# sa_input.net
KiCad netlist of a schematic drawn in EAGLE
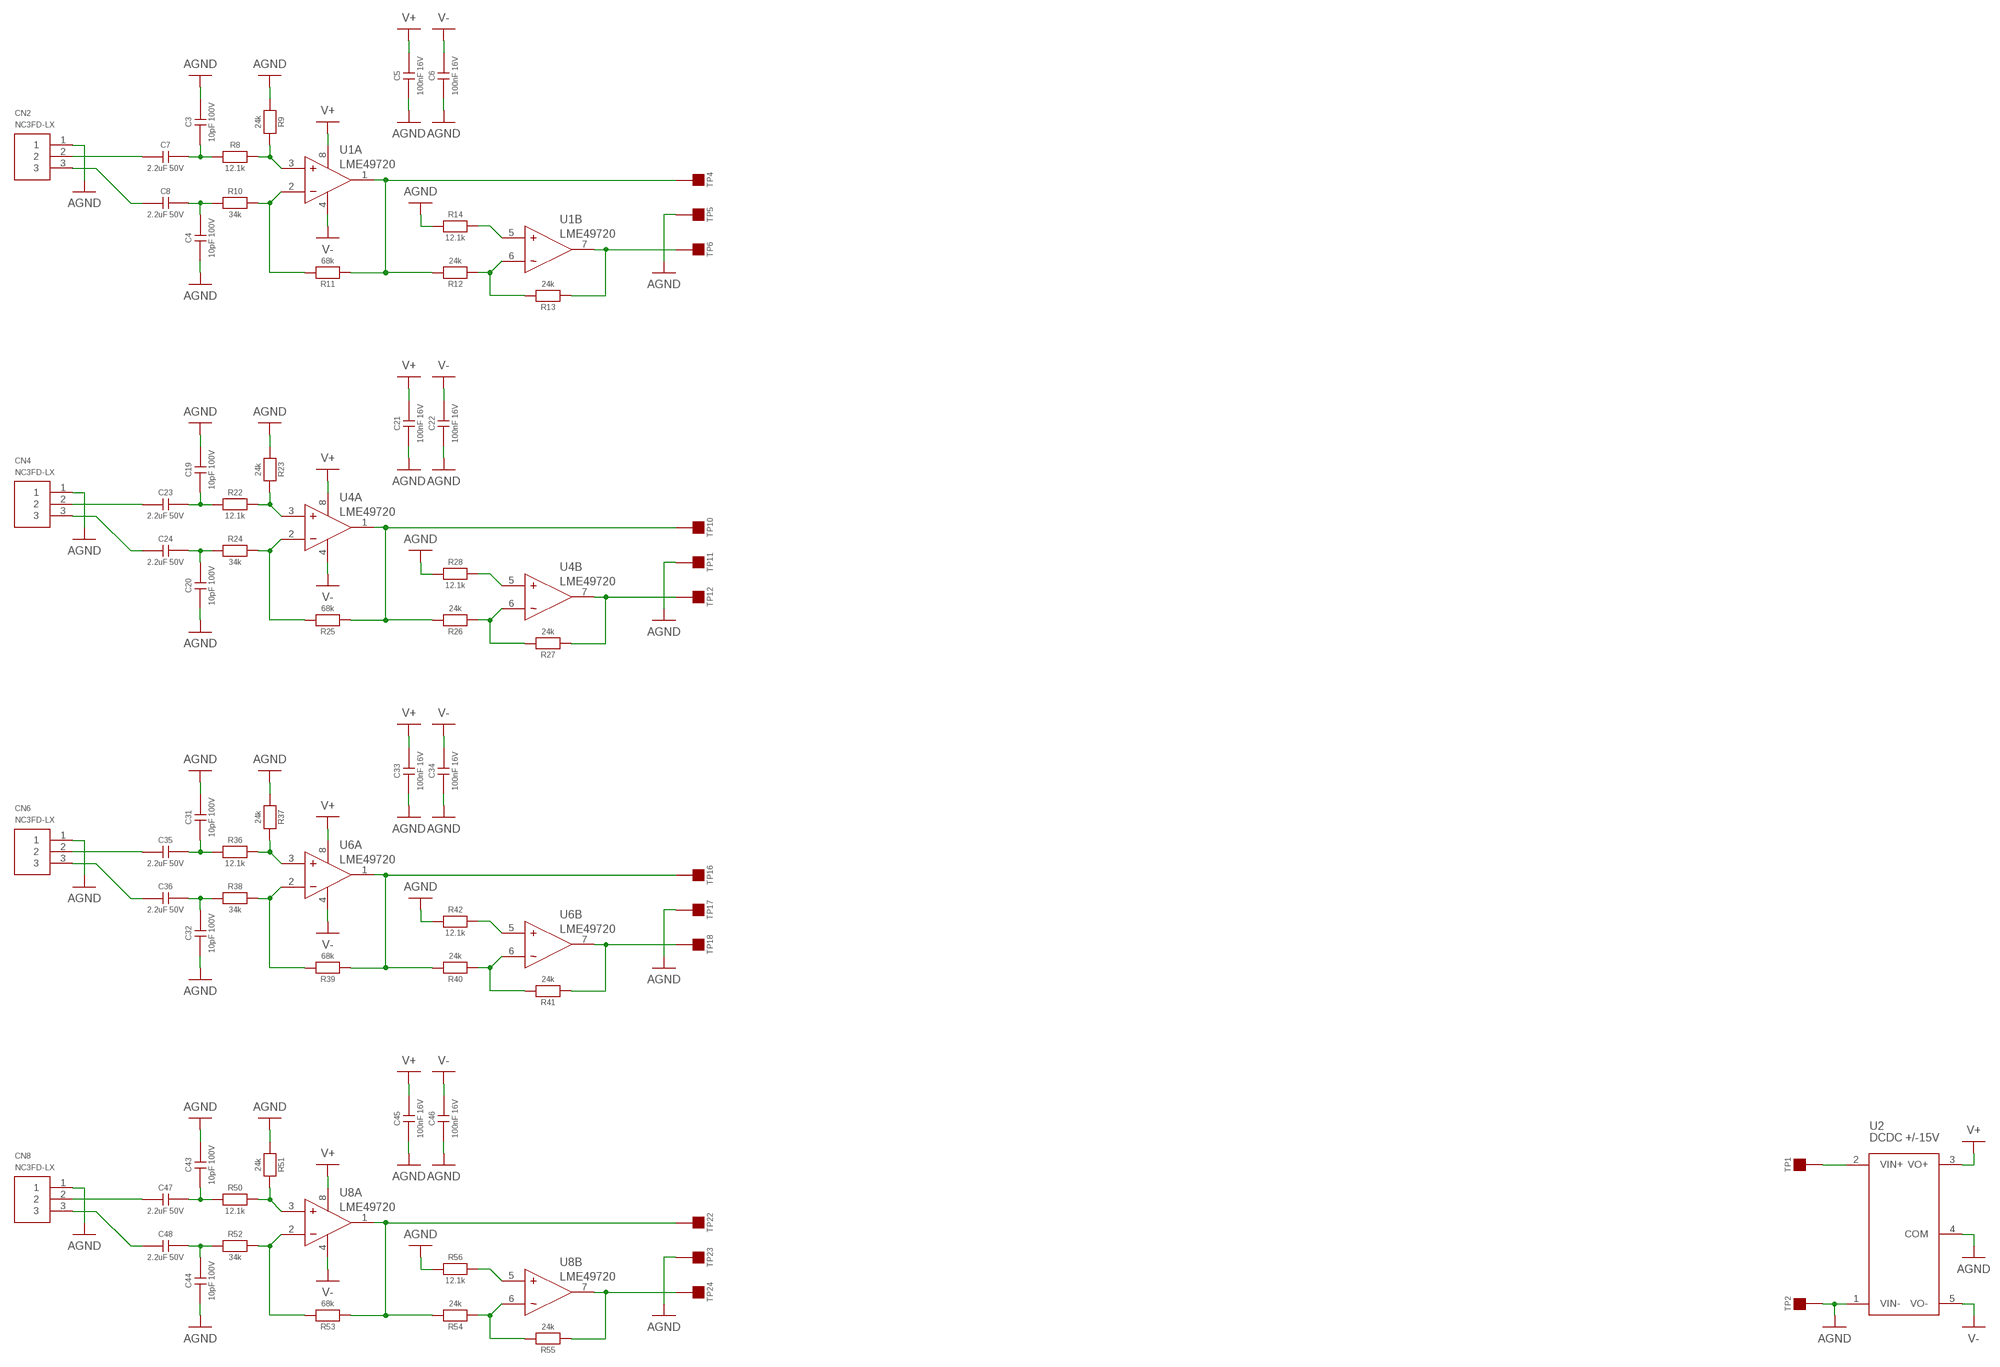
[diagram p0: schematic, sheet 1, part 1 of 2]
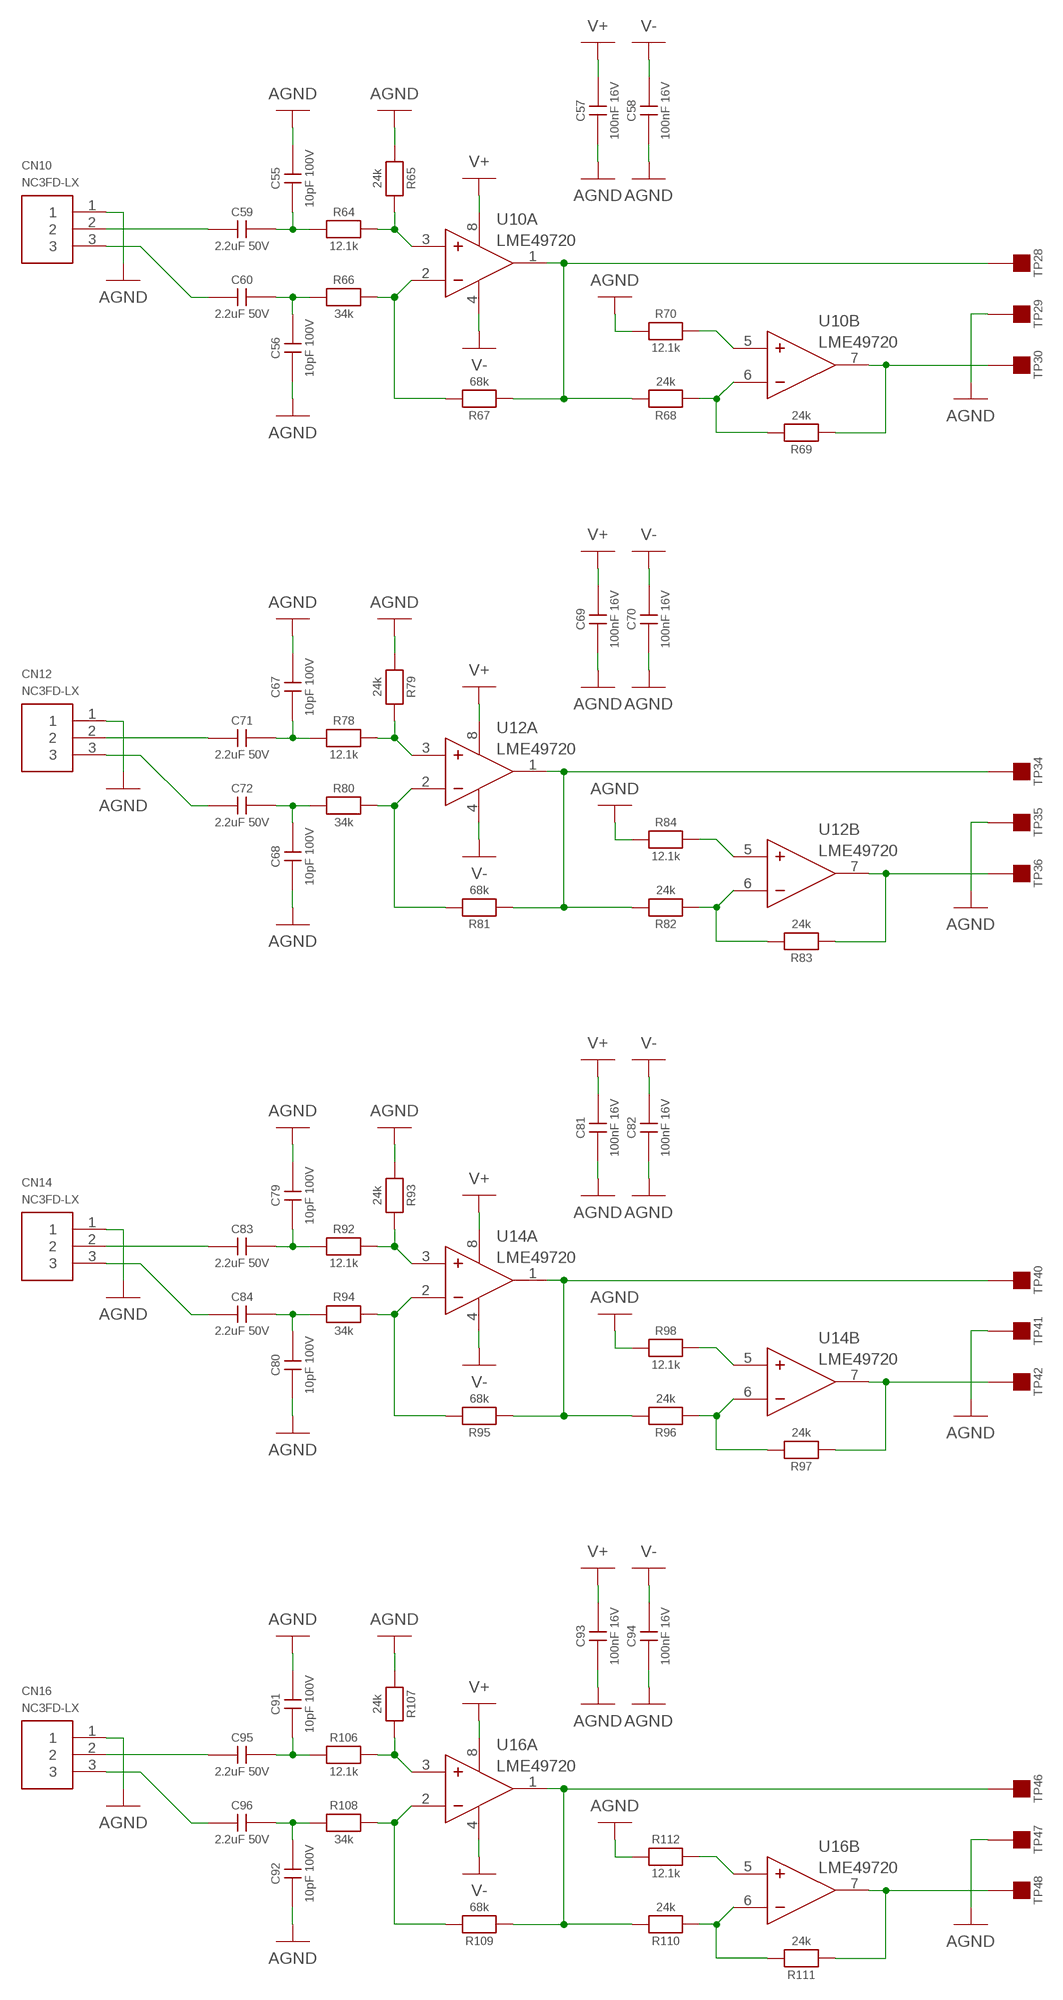
[diagram p1: schematic, sheet 1, part 2 of 2]

(export (version "E")
  (design (tool "Eeschema 10.0.6"))
  (components
    (comp (ref "C3")
      (value "10pF 100V")
      (footprint "eagle-import:0603")
      (libsource (lib "eagle-import") (part "06031A100FAT2A"))
    )
    (comp (ref "C4")
      (value "10pF 100V")
      (footprint "eagle-import:0603")
      (libsource (lib "eagle-import") (part "06031A100FAT2A"))
    )
    (comp (ref "C5")
      (value "100nF 16V")
      (footprint "eagle-import:0603")
      (libsource (lib "eagle-import") (part "CL10B104KO8WPNC"))
    )
    (comp (ref "C6")
      (value "100nF 16V")
      (footprint "eagle-import:0603")
      (libsource (lib "eagle-import") (part "CL10B104KO8WPNC"))
    )
    (comp (ref "C7")
      (value "2.2uF 50V")
      (footprint "eagle-import:5X7.2BOX")
      (libsource (lib "eagle-import") (part "MKS2B042201F00KSSD"))
    )
    (comp (ref "C8")
      (value "2.2uF 50V")
      (footprint "eagle-import:5X7.2BOX")
      (libsource (lib "eagle-import") (part "MKS2B042201F00KSSD"))
    )
    (comp (ref "C19")
      (value "10pF 100V")
      (footprint "eagle-import:0603")
      (libsource (lib "eagle-import") (part "06031A100FAT2A"))
    )
    (comp (ref "C20")
      (value "10pF 100V")
      (footprint "eagle-import:0603")
      (libsource (lib "eagle-import") (part "06031A100FAT2A"))
    )
    (comp (ref "C21")
      (value "100nF 16V")
      (footprint "eagle-import:0603")
      (libsource (lib "eagle-import") (part "CL10B104KO8WPNC"))
    )
    (comp (ref "C22")
      (value "100nF 16V")
      (footprint "eagle-import:0603")
      (libsource (lib "eagle-import") (part "CL10B104KO8WPNC"))
    )
    (comp (ref "C23")
      (value "2.2uF 50V")
      (footprint "eagle-import:5X7.2BOX")
      (libsource (lib "eagle-import") (part "MKS2B042201F00KSSD"))
    )
    (comp (ref "C24")
      (value "2.2uF 50V")
      (footprint "eagle-import:5X7.2BOX")
      (libsource (lib "eagle-import") (part "MKS2B042201F00KSSD"))
    )
    (comp (ref "C31")
      (value "10pF 100V")
      (footprint "eagle-import:0603")
      (libsource (lib "eagle-import") (part "06031A100FAT2A"))
    )
    (comp (ref "C32")
      (value "10pF 100V")
      (footprint "eagle-import:0603")
      (libsource (lib "eagle-import") (part "06031A100FAT2A"))
    )
    (comp (ref "C33")
      (value "100nF 16V")
      (footprint "eagle-import:0603")
      (libsource (lib "eagle-import") (part "CL10B104KO8WPNC"))
    )
    (comp (ref "C34")
      (value "100nF 16V")
      (footprint "eagle-import:0603")
      (libsource (lib "eagle-import") (part "CL10B104KO8WPNC"))
    )
    (comp (ref "C35")
      (value "2.2uF 50V")
      (footprint "eagle-import:5X7.2BOX")
      (libsource (lib "eagle-import") (part "MKS2B042201F00KSSD"))
    )
    (comp (ref "C36")
      (value "2.2uF 50V")
      (footprint "eagle-import:5X7.2BOX")
      (libsource (lib "eagle-import") (part "MKS2B042201F00KSSD"))
    )
    (comp (ref "C43")
      (value "10pF 100V")
      (footprint "eagle-import:0603")
      (libsource (lib "eagle-import") (part "06031A100FAT2A"))
    )
    (comp (ref "C44")
      (value "10pF 100V")
      (footprint "eagle-import:0603")
      (libsource (lib "eagle-import") (part "06031A100FAT2A"))
    )
    (comp (ref "C45")
      (value "100nF 16V")
      (footprint "eagle-import:0603")
      (libsource (lib "eagle-import") (part "CL10B104KO8WPNC"))
    )
    (comp (ref "C46")
      (value "100nF 16V")
      (footprint "eagle-import:0603")
      (libsource (lib "eagle-import") (part "CL10B104KO8WPNC"))
    )
    (comp (ref "C47")
      (value "2.2uF 50V")
      (footprint "eagle-import:5X7.2BOX")
      (libsource (lib "eagle-import") (part "MKS2B042201F00KSSD"))
    )
    (comp (ref "C48")
      (value "2.2uF 50V")
      (footprint "eagle-import:5X7.2BOX")
      (libsource (lib "eagle-import") (part "MKS2B042201F00KSSD"))
    )
    (comp (ref "C55")
      (value "10pF 100V")
      (footprint "eagle-import:0603")
      (libsource (lib "eagle-import") (part "06031A100FAT2A"))
    )
    (comp (ref "C56")
      (value "10pF 100V")
      (footprint "eagle-import:0603")
      (libsource (lib "eagle-import") (part "06031A100FAT2A"))
    )
    (comp (ref "C57")
      (value "100nF 16V")
      (footprint "eagle-import:0603")
      (libsource (lib "eagle-import") (part "CL10B104KO8WPNC"))
    )
    (comp (ref "C58")
      (value "100nF 16V")
      (footprint "eagle-import:0603")
      (libsource (lib "eagle-import") (part "CL10B104KO8WPNC"))
    )
    (comp (ref "C59")
      (value "2.2uF 50V")
      (footprint "eagle-import:5X7.2BOX")
      (libsource (lib "eagle-import") (part "MKS2B042201F00KSSD"))
    )
    (comp (ref "C60")
      (value "2.2uF 50V")
      (footprint "eagle-import:5X7.2BOX")
      (libsource (lib "eagle-import") (part "MKS2B042201F00KSSD"))
    )
    (comp (ref "C67")
      (value "10pF 100V")
      (footprint "eagle-import:0603")
      (libsource (lib "eagle-import") (part "06031A100FAT2A"))
    )
    (comp (ref "C68")
      (value "10pF 100V")
      (footprint "eagle-import:0603")
      (libsource (lib "eagle-import") (part "06031A100FAT2A"))
    )
    (comp (ref "C69")
      (value "100nF 16V")
      (footprint "eagle-import:0603")
      (libsource (lib "eagle-import") (part "CL10B104KO8WPNC"))
    )
    (comp (ref "C70")
      (value "100nF 16V")
      (footprint "eagle-import:0603")
      (libsource (lib "eagle-import") (part "CL10B104KO8WPNC"))
    )
    (comp (ref "C71")
      (value "2.2uF 50V")
      (footprint "eagle-import:5X7.2BOX")
      (libsource (lib "eagle-import") (part "MKS2B042201F00KSSD"))
    )
    (comp (ref "C72")
      (value "2.2uF 50V")
      (footprint "eagle-import:5X7.2BOX")
      (libsource (lib "eagle-import") (part "MKS2B042201F00KSSD"))
    )
    (comp (ref "C79")
      (value "10pF 100V")
      (footprint "eagle-import:0603")
      (libsource (lib "eagle-import") (part "06031A100FAT2A"))
    )
    (comp (ref "C80")
      (value "10pF 100V")
      (footprint "eagle-import:0603")
      (libsource (lib "eagle-import") (part "06031A100FAT2A"))
    )
    (comp (ref "C81")
      (value "100nF 16V")
      (footprint "eagle-import:0603")
      (libsource (lib "eagle-import") (part "CL10B104KO8WPNC"))
    )
    (comp (ref "C82")
      (value "100nF 16V")
      (footprint "eagle-import:0603")
      (libsource (lib "eagle-import") (part "CL10B104KO8WPNC"))
    )
    (comp (ref "C83")
      (value "2.2uF 50V")
      (footprint "eagle-import:5X7.2BOX")
      (libsource (lib "eagle-import") (part "MKS2B042201F00KSSD"))
    )
    (comp (ref "C84")
      (value "2.2uF 50V")
      (footprint "eagle-import:5X7.2BOX")
      (libsource (lib "eagle-import") (part "MKS2B042201F00KSSD"))
    )
    (comp (ref "C91")
      (value "10pF 100V")
      (footprint "eagle-import:0603")
      (libsource (lib "eagle-import") (part "06031A100FAT2A"))
    )
    (comp (ref "C92")
      (value "10pF 100V")
      (footprint "eagle-import:0603")
      (libsource (lib "eagle-import") (part "06031A100FAT2A"))
    )
    (comp (ref "C93")
      (value "100nF 16V")
      (footprint "eagle-import:0603")
      (libsource (lib "eagle-import") (part "CL10B104KO8WPNC"))
    )
    (comp (ref "C94")
      (value "100nF 16V")
      (footprint "eagle-import:0603")
      (libsource (lib "eagle-import") (part "CL10B104KO8WPNC"))
    )
    (comp (ref "C95")
      (value "2.2uF 50V")
      (footprint "eagle-import:5X7.2BOX")
      (libsource (lib "eagle-import") (part "MKS2B042201F00KSSD"))
    )
    (comp (ref "C96")
      (value "2.2uF 50V")
      (footprint "eagle-import:5X7.2BOX")
      (libsource (lib "eagle-import") (part "MKS2B042201F00KSSD"))
    )
    (comp (ref "CN2")
      (value "NC3FD-LX")
      (footprint "eagle-import:NC3FD-LX")
      (libsource (lib "eagle-import") (part "NC3FD-LX"))
    )
    (comp (ref "CN4")
      (value "NC3FD-LX")
      (footprint "eagle-import:NC3FD-LX")
      (libsource (lib "eagle-import") (part "NC3FD-LX"))
    )
    (comp (ref "CN6")
      (value "NC3FD-LX")
      (footprint "eagle-import:NC3FD-LX")
      (libsource (lib "eagle-import") (part "NC3FD-LX"))
    )
    (comp (ref "CN8")
      (value "NC3FD-LX")
      (footprint "eagle-import:NC3FD-LX")
      (libsource (lib "eagle-import") (part "NC3FD-LX"))
    )
    (comp (ref "CN10")
      (value "NC3FD-LX")
      (footprint "eagle-import:NC3FD-LX")
      (libsource (lib "eagle-import") (part "NC3FD-LX"))
    )
    (comp (ref "CN12")
      (value "NC3FD-LX")
      (footprint "eagle-import:NC3FD-LX")
      (libsource (lib "eagle-import") (part "NC3FD-LX"))
    )
    (comp (ref "CN14")
      (value "NC3FD-LX")
      (footprint "eagle-import:NC3FD-LX")
      (libsource (lib "eagle-import") (part "NC3FD-LX"))
    )
    (comp (ref "CN16")
      (value "NC3FD-LX")
      (footprint "eagle-import:NC3FD-LX")
      (libsource (lib "eagle-import") (part "NC3FD-LX"))
    )
    (comp (ref "R8")
      (value "12.1k")
      (footprint "eagle-import:0603")
      (fields
        (field (name "MANUFACTURER") "Vishay Dale")
        (field (name "POWER") "0.1W, 1/10W")
        (field (name "TOLERANCE") "±1%")
      )
      (libsource (lib "eagle-import") (part "CRCW060312K1FKEB"))
    )
    (comp (ref "R9")
      (value "24k")
      (footprint "eagle-import:0603")
      (fields
        (field (name "MANUFACTURER") "Vishay Dale")
        (field (name "POWER") "0.1W, 1/10W")
        (field (name "TOLERANCE") "±1%")
      )
      (libsource (lib "eagle-import") (part "CRCW060324K0FKEA"))
    )
    (comp (ref "R10")
      (value "34k")
      (footprint "eagle-import:0603")
      (fields
        (field (name "MANUFACTURER") "Vishay Dale")
        (field (name "POWER") "0.1W, 1/10W")
        (field (name "TOLERANCE") "±1%")
      )
      (libsource (lib "eagle-import") (part "CRCW060334K0FKEA"))
    )
    (comp (ref "R11")
      (value "68k")
      (footprint "eagle-import:0603")
      (fields
        (field (name "MANUFACTURER") "Vishay Dale")
        (field (name "POWER") "0.1W, 1/10W")
        (field (name "TOLERANCE") "±1%")
      )
      (libsource (lib "eagle-import") (part "CRCW060368K0FKEA"))
    )
    (comp (ref "R12")
      (value "24k")
      (footprint "eagle-import:0603")
      (fields
        (field (name "MANUFACTURER") "Vishay Dale")
        (field (name "POWER") "0.1W, 1/10W")
        (field (name "TOLERANCE") "±1%")
      )
      (libsource (lib "eagle-import") (part "CRCW060324K0FKEA"))
    )
    (comp (ref "R13")
      (value "24k")
      (footprint "eagle-import:0603")
      (fields
        (field (name "MANUFACTURER") "Vishay Dale")
        (field (name "POWER") "0.1W, 1/10W")
        (field (name "TOLERANCE") "±1%")
      )
      (libsource (lib "eagle-import") (part "CRCW060324K0FKEA"))
    )
    (comp (ref "R14")
      (value "12.1k")
      (footprint "eagle-import:0603")
      (fields
        (field (name "MANUFACTURER") "Vishay Dale")
        (field (name "POWER") "0.1W, 1/10W")
        (field (name "TOLERANCE") "±1%")
      )
      (libsource (lib "eagle-import") (part "CRCW060312K1FKEB"))
    )
    (comp (ref "R22")
      (value "12.1k")
      (footprint "eagle-import:0603")
      (fields
        (field (name "MANUFACTURER") "Vishay Dale")
        (field (name "POWER") "0.1W, 1/10W")
        (field (name "TOLERANCE") "±1%")
      )
      (libsource (lib "eagle-import") (part "CRCW060312K1FKEB"))
    )
    (comp (ref "R23")
      (value "24k")
      (footprint "eagle-import:0603")
      (fields
        (field (name "MANUFACTURER") "Vishay Dale")
        (field (name "POWER") "0.1W, 1/10W")
        (field (name "TOLERANCE") "±1%")
      )
      (libsource (lib "eagle-import") (part "CRCW060324K0FKEA"))
    )
    (comp (ref "R24")
      (value "34k")
      (footprint "eagle-import:0603")
      (fields
        (field (name "MANUFACTURER") "Vishay Dale")
        (field (name "POWER") "0.1W, 1/10W")
        (field (name "TOLERANCE") "±1%")
      )
      (libsource (lib "eagle-import") (part "CRCW060334K0FKEA"))
    )
    (comp (ref "R25")
      (value "68k")
      (footprint "eagle-import:0603")
      (fields
        (field (name "MANUFACTURER") "Vishay Dale")
        (field (name "POWER") "0.1W, 1/10W")
        (field (name "TOLERANCE") "±1%")
      )
      (libsource (lib "eagle-import") (part "CRCW060368K0FKEA"))
    )
    (comp (ref "R26")
      (value "24k")
      (footprint "eagle-import:0603")
      (fields
        (field (name "MANUFACTURER") "Vishay Dale")
        (field (name "POWER") "0.1W, 1/10W")
        (field (name "TOLERANCE") "±1%")
      )
      (libsource (lib "eagle-import") (part "CRCW060324K0FKEA"))
    )
    (comp (ref "R27")
      (value "24k")
      (footprint "eagle-import:0603")
      (fields
        (field (name "MANUFACTURER") "Vishay Dale")
        (field (name "POWER") "0.1W, 1/10W")
        (field (name "TOLERANCE") "±1%")
      )
      (libsource (lib "eagle-import") (part "CRCW060324K0FKEA"))
    )
    (comp (ref "R28")
      (value "12.1k")
      (footprint "eagle-import:0603")
      (fields
        (field (name "MANUFACTURER") "Vishay Dale")
        (field (name "POWER") "0.1W, 1/10W")
        (field (name "TOLERANCE") "±1%")
      )
      (libsource (lib "eagle-import") (part "CRCW060312K1FKEB"))
    )
    (comp (ref "R36")
      (value "12.1k")
      (footprint "eagle-import:0603")
      (fields
        (field (name "MANUFACTURER") "Vishay Dale")
        (field (name "POWER") "0.1W, 1/10W")
        (field (name "TOLERANCE") "±1%")
      )
      (libsource (lib "eagle-import") (part "CRCW060312K1FKEB"))
    )
    (comp (ref "R37")
      (value "24k")
      (footprint "eagle-import:0603")
      (fields
        (field (name "MANUFACTURER") "Vishay Dale")
        (field (name "POWER") "0.1W, 1/10W")
        (field (name "TOLERANCE") "±1%")
      )
      (libsource (lib "eagle-import") (part "CRCW060324K0FKEA"))
    )
    (comp (ref "R38")
      (value "34k")
      (footprint "eagle-import:0603")
      (fields
        (field (name "MANUFACTURER") "Vishay Dale")
        (field (name "POWER") "0.1W, 1/10W")
        (field (name "TOLERANCE") "±1%")
      )
      (libsource (lib "eagle-import") (part "CRCW060334K0FKEA"))
    )
    (comp (ref "R39")
      (value "68k")
      (footprint "eagle-import:0603")
      (fields
        (field (name "MANUFACTURER") "Vishay Dale")
        (field (name "POWER") "0.1W, 1/10W")
        (field (name "TOLERANCE") "±1%")
      )
      (libsource (lib "eagle-import") (part "CRCW060368K0FKEA"))
    )
    (comp (ref "R40")
      (value "24k")
      (footprint "eagle-import:0603")
      (fields
        (field (name "MANUFACTURER") "Vishay Dale")
        (field (name "POWER") "0.1W, 1/10W")
        (field (name "TOLERANCE") "±1%")
      )
      (libsource (lib "eagle-import") (part "CRCW060324K0FKEA"))
    )
    (comp (ref "R41")
      (value "24k")
      (footprint "eagle-import:0603")
      (fields
        (field (name "MANUFACTURER") "Vishay Dale")
        (field (name "POWER") "0.1W, 1/10W")
        (field (name "TOLERANCE") "±1%")
      )
      (libsource (lib "eagle-import") (part "CRCW060324K0FKEA"))
    )
    (comp (ref "R42")
      (value "12.1k")
      (footprint "eagle-import:0603")
      (fields
        (field (name "MANUFACTURER") "Vishay Dale")
        (field (name "POWER") "0.1W, 1/10W")
        (field (name "TOLERANCE") "±1%")
      )
      (libsource (lib "eagle-import") (part "CRCW060312K1FKEB"))
    )
    (comp (ref "R50")
      (value "12.1k")
      (footprint "eagle-import:0603")
      (fields
        (field (name "MANUFACTURER") "Vishay Dale")
        (field (name "POWER") "0.1W, 1/10W")
        (field (name "TOLERANCE") "±1%")
      )
      (libsource (lib "eagle-import") (part "CRCW060312K1FKEB"))
    )
    (comp (ref "R51")
      (value "24k")
      (footprint "eagle-import:0603")
      (fields
        (field (name "MANUFACTURER") "Vishay Dale")
        (field (name "POWER") "0.1W, 1/10W")
        (field (name "TOLERANCE") "±1%")
      )
      (libsource (lib "eagle-import") (part "CRCW060324K0FKEA"))
    )
    (comp (ref "R52")
      (value "34k")
      (footprint "eagle-import:0603")
      (fields
        (field (name "MANUFACTURER") "Vishay Dale")
        (field (name "POWER") "0.1W, 1/10W")
        (field (name "TOLERANCE") "±1%")
      )
      (libsource (lib "eagle-import") (part "CRCW060334K0FKEA"))
    )
    (comp (ref "R53")
      (value "68k")
      (footprint "eagle-import:0603")
      (fields
        (field (name "MANUFACTURER") "Vishay Dale")
        (field (name "POWER") "0.1W, 1/10W")
        (field (name "TOLERANCE") "±1%")
      )
      (libsource (lib "eagle-import") (part "CRCW060368K0FKEA"))
    )
    (comp (ref "R54")
      (value "24k")
      (footprint "eagle-import:0603")
      (fields
        (field (name "MANUFACTURER") "Vishay Dale")
        (field (name "POWER") "0.1W, 1/10W")
        (field (name "TOLERANCE") "±1%")
      )
      (libsource (lib "eagle-import") (part "CRCW060324K0FKEA"))
    )
    (comp (ref "R55")
      (value "24k")
      (footprint "eagle-import:0603")
      (fields
        (field (name "MANUFACTURER") "Vishay Dale")
        (field (name "POWER") "0.1W, 1/10W")
        (field (name "TOLERANCE") "±1%")
      )
      (libsource (lib "eagle-import") (part "CRCW060324K0FKEA"))
    )
    (comp (ref "R56")
      (value "12.1k")
      (footprint "eagle-import:0603")
      (fields
        (field (name "MANUFACTURER") "Vishay Dale")
        (field (name "POWER") "0.1W, 1/10W")
        (field (name "TOLERANCE") "±1%")
      )
      (libsource (lib "eagle-import") (part "CRCW060312K1FKEB"))
    )
    (comp (ref "R64")
      (value "12.1k")
      (footprint "eagle-import:0603")
      (fields
        (field (name "MANUFACTURER") "Vishay Dale")
        (field (name "POWER") "0.1W, 1/10W")
        (field (name "TOLERANCE") "±1%")
      )
      (libsource (lib "eagle-import") (part "CRCW060312K1FKEB"))
    )
    (comp (ref "R65")
      (value "24k")
      (footprint "eagle-import:0603")
      (fields
        (field (name "MANUFACTURER") "Vishay Dale")
        (field (name "POWER") "0.1W, 1/10W")
        (field (name "TOLERANCE") "±1%")
      )
      (libsource (lib "eagle-import") (part "CRCW060324K0FKEA"))
    )
    (comp (ref "R66")
      (value "34k")
      (footprint "eagle-import:0603")
      (fields
        (field (name "MANUFACTURER") "Vishay Dale")
        (field (name "POWER") "0.1W, 1/10W")
        (field (name "TOLERANCE") "±1%")
      )
      (libsource (lib "eagle-import") (part "CRCW060334K0FKEA"))
    )
    (comp (ref "R67")
      (value "68k")
      (footprint "eagle-import:0603")
      (fields
        (field (name "MANUFACTURER") "Vishay Dale")
        (field (name "POWER") "0.1W, 1/10W")
        (field (name "TOLERANCE") "±1%")
      )
      (libsource (lib "eagle-import") (part "CRCW060368K0FKEA"))
    )
    (comp (ref "R68")
      (value "24k")
      (footprint "eagle-import:0603")
      (fields
        (field (name "MANUFACTURER") "Vishay Dale")
        (field (name "POWER") "0.1W, 1/10W")
        (field (name "TOLERANCE") "±1%")
      )
      (libsource (lib "eagle-import") (part "CRCW060324K0FKEA"))
    )
    (comp (ref "R69")
      (value "24k")
      (footprint "eagle-import:0603")
      (fields
        (field (name "MANUFACTURER") "Vishay Dale")
        (field (name "POWER") "0.1W, 1/10W")
        (field (name "TOLERANCE") "±1%")
      )
      (libsource (lib "eagle-import") (part "CRCW060324K0FKEA"))
    )
    (comp (ref "R70")
      (value "12.1k")
      (footprint "eagle-import:0603")
      (fields
        (field (name "MANUFACTURER") "Vishay Dale")
        (field (name "POWER") "0.1W, 1/10W")
        (field (name "TOLERANCE") "±1%")
      )
      (libsource (lib "eagle-import") (part "CRCW060312K1FKEB"))
    )
    (comp (ref "R78")
      (value "12.1k")
      (footprint "eagle-import:0603")
      (fields
        (field (name "MANUFACTURER") "Vishay Dale")
        (field (name "POWER") "0.1W, 1/10W")
        (field (name "TOLERANCE") "±1%")
      )
      (libsource (lib "eagle-import") (part "CRCW060312K1FKEB"))
    )
    (comp (ref "R79")
      (value "24k")
      (footprint "eagle-import:0603")
      (fields
        (field (name "MANUFACTURER") "Vishay Dale")
        (field (name "POWER") "0.1W, 1/10W")
        (field (name "TOLERANCE") "±1%")
      )
      (libsource (lib "eagle-import") (part "CRCW060324K0FKEA"))
    )
    (comp (ref "R80")
      (value "34k")
      (footprint "eagle-import:0603")
      (fields
        (field (name "MANUFACTURER") "Vishay Dale")
        (field (name "POWER") "0.1W, 1/10W")
        (field (name "TOLERANCE") "±1%")
      )
      (libsource (lib "eagle-import") (part "CRCW060334K0FKEA"))
    )
    (comp (ref "R81")
      (value "68k")
      (footprint "eagle-import:0603")
      (fields
        (field (name "MANUFACTURER") "Vishay Dale")
        (field (name "POWER") "0.1W, 1/10W")
        (field (name "TOLERANCE") "±1%")
      )
      (libsource (lib "eagle-import") (part "CRCW060368K0FKEA"))
    )
    (comp (ref "R82")
      (value "24k")
      (footprint "eagle-import:0603")
      (fields
        (field (name "MANUFACTURER") "Vishay Dale")
        (field (name "POWER") "0.1W, 1/10W")
        (field (name "TOLERANCE") "±1%")
      )
      (libsource (lib "eagle-import") (part "CRCW060324K0FKEA"))
    )
    (comp (ref "R83")
      (value "24k")
      (footprint "eagle-import:0603")
      (fields
        (field (name "MANUFACTURER") "Vishay Dale")
        (field (name "POWER") "0.1W, 1/10W")
        (field (name "TOLERANCE") "±1%")
      )
      (libsource (lib "eagle-import") (part "CRCW060324K0FKEA"))
    )
    (comp (ref "R84")
      (value "12.1k")
      (footprint "eagle-import:0603")
      (fields
        (field (name "MANUFACTURER") "Vishay Dale")
        (field (name "POWER") "0.1W, 1/10W")
        (field (name "TOLERANCE") "±1%")
      )
      (libsource (lib "eagle-import") (part "CRCW060312K1FKEB"))
    )
    (comp (ref "R92")
      (value "12.1k")
      (footprint "eagle-import:0603")
      (fields
        (field (name "MANUFACTURER") "Vishay Dale")
        (field (name "POWER") "0.1W, 1/10W")
        (field (name "TOLERANCE") "±1%")
      )
      (libsource (lib "eagle-import") (part "CRCW060312K1FKEB"))
    )
    (comp (ref "R93")
      (value "24k")
      (footprint "eagle-import:0603")
      (fields
        (field (name "MANUFACTURER") "Vishay Dale")
        (field (name "POWER") "0.1W, 1/10W")
        (field (name "TOLERANCE") "±1%")
      )
      (libsource (lib "eagle-import") (part "CRCW060324K0FKEA"))
    )
    (comp (ref "R94")
      (value "34k")
      (footprint "eagle-import:0603")
      (fields
        (field (name "MANUFACTURER") "Vishay Dale")
        (field (name "POWER") "0.1W, 1/10W")
        (field (name "TOLERANCE") "±1%")
      )
      (libsource (lib "eagle-import") (part "CRCW060334K0FKEA"))
    )
    (comp (ref "R95")
      (value "68k")
      (footprint "eagle-import:0603")
      (fields
        (field (name "MANUFACTURER") "Vishay Dale")
        (field (name "POWER") "0.1W, 1/10W")
        (field (name "TOLERANCE") "±1%")
      )
      (libsource (lib "eagle-import") (part "CRCW060368K0FKEA"))
    )
    (comp (ref "R96")
      (value "24k")
      (footprint "eagle-import:0603")
      (fields
        (field (name "MANUFACTURER") "Vishay Dale")
        (field (name "POWER") "0.1W, 1/10W")
        (field (name "TOLERANCE") "±1%")
      )
      (libsource (lib "eagle-import") (part "CRCW060324K0FKEA"))
    )
    (comp (ref "R97")
      (value "24k")
      (footprint "eagle-import:0603")
      (fields
        (field (name "MANUFACTURER") "Vishay Dale")
        (field (name "POWER") "0.1W, 1/10W")
        (field (name "TOLERANCE") "±1%")
      )
      (libsource (lib "eagle-import") (part "CRCW060324K0FKEA"))
    )
    (comp (ref "R98")
      (value "12.1k")
      (footprint "eagle-import:0603")
      (fields
        (field (name "MANUFACTURER") "Vishay Dale")
        (field (name "POWER") "0.1W, 1/10W")
        (field (name "TOLERANCE") "±1%")
      )
      (libsource (lib "eagle-import") (part "CRCW060312K1FKEB"))
    )
    (comp (ref "R106")
      (value "12.1k")
      (footprint "eagle-import:0603")
      (fields
        (field (name "MANUFACTURER") "Vishay Dale")
        (field (name "POWER") "0.1W, 1/10W")
        (field (name "TOLERANCE") "±1%")
      )
      (libsource (lib "eagle-import") (part "CRCW060312K1FKEB"))
    )
    (comp (ref "R107")
      (value "24k")
      (footprint "eagle-import:0603")
      (fields
        (field (name "MANUFACTURER") "Vishay Dale")
        (field (name "POWER") "0.1W, 1/10W")
        (field (name "TOLERANCE") "±1%")
      )
      (libsource (lib "eagle-import") (part "CRCW060324K0FKEA"))
    )
    (comp (ref "R108")
      (value "34k")
      (footprint "eagle-import:0603")
      (fields
        (field (name "MANUFACTURER") "Vishay Dale")
        (field (name "POWER") "0.1W, 1/10W")
        (field (name "TOLERANCE") "±1%")
      )
      (libsource (lib "eagle-import") (part "CRCW060334K0FKEA"))
    )
    (comp (ref "R109")
      (value "68k")
      (footprint "eagle-import:0603")
      (fields
        (field (name "MANUFACTURER") "Vishay Dale")
        (field (name "POWER") "0.1W, 1/10W")
        (field (name "TOLERANCE") "±1%")
      )
      (libsource (lib "eagle-import") (part "CRCW060368K0FKEA"))
    )
    (comp (ref "R110")
      (value "24k")
      (footprint "eagle-import:0603")
      (fields
        (field (name "MANUFACTURER") "Vishay Dale")
        (field (name "POWER") "0.1W, 1/10W")
        (field (name "TOLERANCE") "±1%")
      )
      (libsource (lib "eagle-import") (part "CRCW060324K0FKEA"))
    )
    (comp (ref "R111")
      (value "24k")
      (footprint "eagle-import:0603")
      (fields
        (field (name "MANUFACTURER") "Vishay Dale")
        (field (name "POWER") "0.1W, 1/10W")
        (field (name "TOLERANCE") "±1%")
      )
      (libsource (lib "eagle-import") (part "CRCW060324K0FKEA"))
    )
    (comp (ref "R112")
      (value "12.1k")
      (footprint "eagle-import:0603")
      (fields
        (field (name "MANUFACTURER") "Vishay Dale")
        (field (name "POWER") "0.1W, 1/10W")
        (field (name "TOLERANCE") "±1%")
      )
      (libsource (lib "eagle-import") (part "CRCW060312K1FKEB"))
    )
    (comp (ref "TP1")
      (value "TEST_POINT_SQUARE")
      (footprint "eagle-import:OSPREY_HSS_PAD")
      (libsource (lib "eagle-import") (part "TEST_POINT_SQUARE"))
    )
    (comp (ref "TP2")
      (value "TEST_POINT_SQUARE")
      (footprint "eagle-import:OSPREY_HSS_PAD")
      (libsource (lib "eagle-import") (part "TEST_POINT_SQUARE"))
    )
    (comp (ref "TP4")
      (value "TEST_POINT_SQUARE")
      (footprint "eagle-import:OSPREY_HSS_PAD")
      (libsource (lib "eagle-import") (part "TEST_POINT_SQUARE"))
    )
    (comp (ref "TP5")
      (value "TEST_POINT_SQUARE")
      (footprint "eagle-import:OSPREY_HSS_PAD")
      (libsource (lib "eagle-import") (part "TEST_POINT_SQUARE"))
    )
    (comp (ref "TP6")
      (value "TEST_POINT_SQUARE")
      (footprint "eagle-import:OSPREY_HSS_PAD")
      (libsource (lib "eagle-import") (part "TEST_POINT_SQUARE"))
    )
    (comp (ref "TP10")
      (value "TEST_POINT_SQUARE")
      (footprint "eagle-import:OSPREY_HSS_PAD")
      (libsource (lib "eagle-import") (part "TEST_POINT_SQUARE"))
    )
    (comp (ref "TP11")
      (value "TEST_POINT_SQUARE")
      (footprint "eagle-import:OSPREY_HSS_PAD")
      (libsource (lib "eagle-import") (part "TEST_POINT_SQUARE"))
    )
    (comp (ref "TP12")
      (value "TEST_POINT_SQUARE")
      (footprint "eagle-import:OSPREY_HSS_PAD")
      (libsource (lib "eagle-import") (part "TEST_POINT_SQUARE"))
    )
    (comp (ref "TP16")
      (value "TEST_POINT_SQUARE")
      (footprint "eagle-import:OSPREY_HSS_PAD")
      (libsource (lib "eagle-import") (part "TEST_POINT_SQUARE"))
    )
    (comp (ref "TP17")
      (value "TEST_POINT_SQUARE")
      (footprint "eagle-import:OSPREY_HSS_PAD")
      (libsource (lib "eagle-import") (part "TEST_POINT_SQUARE"))
    )
    (comp (ref "TP18")
      (value "TEST_POINT_SQUARE")
      (footprint "eagle-import:OSPREY_HSS_PAD")
      (libsource (lib "eagle-import") (part "TEST_POINT_SQUARE"))
    )
    (comp (ref "TP22")
      (value "TEST_POINT_SQUARE")
      (footprint "eagle-import:OSPREY_HSS_PAD")
      (libsource (lib "eagle-import") (part "TEST_POINT_SQUARE"))
    )
    (comp (ref "TP23")
      (value "TEST_POINT_SQUARE")
      (footprint "eagle-import:OSPREY_HSS_PAD")
      (libsource (lib "eagle-import") (part "TEST_POINT_SQUARE"))
    )
    (comp (ref "TP24")
      (value "TEST_POINT_SQUARE")
      (footprint "eagle-import:OSPREY_HSS_PAD")
      (libsource (lib "eagle-import") (part "TEST_POINT_SQUARE"))
    )
    (comp (ref "TP28")
      (value "TEST_POINT_SQUARE")
      (footprint "eagle-import:OSPREY_HSS_PAD")
      (libsource (lib "eagle-import") (part "TEST_POINT_SQUARE"))
    )
    (comp (ref "TP29")
      (value "TEST_POINT_SQUARE")
      (footprint "eagle-import:OSPREY_HSS_PAD")
      (libsource (lib "eagle-import") (part "TEST_POINT_SQUARE"))
    )
    (comp (ref "TP30")
      (value "TEST_POINT_SQUARE")
      (footprint "eagle-import:OSPREY_HSS_PAD")
      (libsource (lib "eagle-import") (part "TEST_POINT_SQUARE"))
    )
    (comp (ref "TP34")
      (value "TEST_POINT_SQUARE")
      (footprint "eagle-import:OSPREY_HSS_PAD")
      (libsource (lib "eagle-import") (part "TEST_POINT_SQUARE"))
    )
    (comp (ref "TP35")
      (value "TEST_POINT_SQUARE")
      (footprint "eagle-import:OSPREY_HSS_PAD")
      (libsource (lib "eagle-import") (part "TEST_POINT_SQUARE"))
    )
    (comp (ref "TP36")
      (value "TEST_POINT_SQUARE")
      (footprint "eagle-import:OSPREY_HSS_PAD")
      (libsource (lib "eagle-import") (part "TEST_POINT_SQUARE"))
    )
    (comp (ref "TP40")
      (value "TEST_POINT_SQUARE")
      (footprint "eagle-import:OSPREY_HSS_PAD")
      (libsource (lib "eagle-import") (part "TEST_POINT_SQUARE"))
    )
    (comp (ref "TP41")
      (value "TEST_POINT_SQUARE")
      (footprint "eagle-import:OSPREY_HSS_PAD")
      (libsource (lib "eagle-import") (part "TEST_POINT_SQUARE"))
    )
    (comp (ref "TP42")
      (value "TEST_POINT_SQUARE")
      (footprint "eagle-import:OSPREY_HSS_PAD")
      (libsource (lib "eagle-import") (part "TEST_POINT_SQUARE"))
    )
    (comp (ref "TP46")
      (value "TEST_POINT_SQUARE")
      (footprint "eagle-import:OSPREY_HSS_PAD")
      (libsource (lib "eagle-import") (part "TEST_POINT_SQUARE"))
    )
    (comp (ref "TP47")
      (value "TEST_POINT_SQUARE")
      (footprint "eagle-import:OSPREY_HSS_PAD")
      (libsource (lib "eagle-import") (part "TEST_POINT_SQUARE"))
    )
    (comp (ref "TP48")
      (value "TEST_POINT_SQUARE")
      (footprint "eagle-import:OSPREY_HSS_PAD")
      (libsource (lib "eagle-import") (part "TEST_POINT_SQUARE"))
    )
    (comp (ref "U1")
      (value "LME49720")
      (footprint "eagle-import:SO8")
      (libsource (lib "eagle-import") (part "LME49720MA/NOPB"))
    )
    (comp (ref "U2")
      (value "DCDC +/-15V")
      (footprint "eagle-import:PDQE10")
      (libsource (lib "eagle-import") (part "PDQE10-Q48-D15-D"))
    )
    (comp (ref "U4")
      (value "LME49720")
      (footprint "eagle-import:SO8")
      (libsource (lib "eagle-import") (part "LME49720MA/NOPB"))
    )
    (comp (ref "U6")
      (value "LME49720")
      (footprint "eagle-import:SO8")
      (libsource (lib "eagle-import") (part "LME49720MA/NOPB"))
    )
    (comp (ref "U8")
      (value "LME49720")
      (footprint "eagle-import:SO8")
      (libsource (lib "eagle-import") (part "LME49720MA/NOPB"))
    )
    (comp (ref "U10")
      (value "LME49720")
      (footprint "eagle-import:SO8")
      (libsource (lib "eagle-import") (part "LME49720MA/NOPB"))
    )
    (comp (ref "U12")
      (value "LME49720")
      (footprint "eagle-import:SO8")
      (libsource (lib "eagle-import") (part "LME49720MA/NOPB"))
    )
    (comp (ref "U14")
      (value "LME49720")
      (footprint "eagle-import:SO8")
      (libsource (lib "eagle-import") (part "LME49720MA/NOPB"))
    )
    (comp (ref "U16")
      (value "LME49720")
      (footprint "eagle-import:SO8")
      (libsource (lib "eagle-import") (part "LME49720MA/NOPB"))
    )
  )
  (nets
    (net (code "1") (name "AGND") (class "Default")
      (node (ref "C19") (pin "1") (pinfunction "1_1") (pintype "bidirectional"))
      (node (ref "C20") (pin "1") (pinfunction "1_1") (pintype "bidirectional"))
      (node (ref "C21") (pin "1") (pinfunction "1_1") (pintype "bidirectional"))
      (node (ref "C22") (pin "1") (pinfunction "1_1") (pintype "bidirectional"))
      (node (ref "C3") (pin "1") (pinfunction "1_1") (pintype "bidirectional"))
      (node (ref "C31") (pin "1") (pinfunction "1_1") (pintype "bidirectional"))
      (node (ref "C32") (pin "1") (pinfunction "1_1") (pintype "bidirectional"))
      (node (ref "C33") (pin "1") (pinfunction "1_1") (pintype "bidirectional"))
      (node (ref "C34") (pin "1") (pinfunction "1_1") (pintype "bidirectional"))
      (node (ref "C4") (pin "1") (pinfunction "1_1") (pintype "bidirectional"))
      (node (ref "C43") (pin "1") (pinfunction "1_1") (pintype "bidirectional"))
      (node (ref "C44") (pin "1") (pinfunction "1_1") (pintype "bidirectional"))
      (node (ref "C45") (pin "1") (pinfunction "1_1") (pintype "bidirectional"))
      (node (ref "C46") (pin "1") (pinfunction "1_1") (pintype "bidirectional"))
      (node (ref "C5") (pin "1") (pinfunction "1_1") (pintype "bidirectional"))
      (node (ref "C55") (pin "1") (pinfunction "1_1") (pintype "bidirectional"))
      (node (ref "C56") (pin "1") (pinfunction "1_1") (pintype "bidirectional"))
      (node (ref "C57") (pin "1") (pinfunction "1_1") (pintype "bidirectional"))
      (node (ref "C58") (pin "1") (pinfunction "1_1") (pintype "bidirectional"))
      (node (ref "C6") (pin "1") (pinfunction "1_1") (pintype "bidirectional"))
      (node (ref "C67") (pin "1") (pinfunction "1_1") (pintype "bidirectional"))
      (node (ref "C68") (pin "1") (pinfunction "1_1") (pintype "bidirectional"))
      (node (ref "C69") (pin "1") (pinfunction "1_1") (pintype "bidirectional"))
      (node (ref "C70") (pin "1") (pinfunction "1_1") (pintype "bidirectional"))
      (node (ref "C79") (pin "1") (pinfunction "1_1") (pintype "bidirectional"))
      (node (ref "C80") (pin "1") (pinfunction "1_1") (pintype "bidirectional"))
      (node (ref "C81") (pin "1") (pinfunction "1_1") (pintype "bidirectional"))
      (node (ref "C82") (pin "1") (pinfunction "1_1") (pintype "bidirectional"))
      (node (ref "C91") (pin "1") (pinfunction "1_1") (pintype "bidirectional"))
      (node (ref "C92") (pin "1") (pinfunction "1_1") (pintype "bidirectional"))
      (node (ref "C93") (pin "1") (pinfunction "1_1") (pintype "bidirectional"))
      (node (ref "C94") (pin "1") (pinfunction "1_1") (pintype "bidirectional"))
      (node (ref "CN10") (pin "1") (pinfunction "1_1") (pintype "bidirectional"))
      (node (ref "CN12") (pin "1") (pinfunction "1_1") (pintype "bidirectional"))
      (node (ref "CN14") (pin "1") (pinfunction "1_1") (pintype "bidirectional"))
      (node (ref "CN16") (pin "1") (pinfunction "1_1") (pintype "bidirectional"))
      (node (ref "CN2") (pin "1") (pinfunction "1_1") (pintype "bidirectional"))
      (node (ref "CN4") (pin "1") (pinfunction "1_1") (pintype "bidirectional"))
      (node (ref "CN6") (pin "1") (pinfunction "1_1") (pintype "bidirectional"))
      (node (ref "CN8") (pin "1") (pinfunction "1_1") (pintype "bidirectional"))
      (node (ref "R107") (pin "1") (pinfunction "1_1") (pintype "bidirectional"))
      (node (ref "R112") (pin "1") (pinfunction "1_1") (pintype "bidirectional"))
      (node (ref "R14") (pin "1") (pinfunction "1_1") (pintype "bidirectional"))
      (node (ref "R23") (pin "1") (pinfunction "1_1") (pintype "bidirectional"))
      (node (ref "R28") (pin "1") (pinfunction "1_1") (pintype "bidirectional"))
      (node (ref "R37") (pin "1") (pinfunction "1_1") (pintype "bidirectional"))
      (node (ref "R42") (pin "1") (pinfunction "1_1") (pintype "bidirectional"))
      (node (ref "R51") (pin "1") (pinfunction "1_1") (pintype "bidirectional"))
      (node (ref "R56") (pin "1") (pinfunction "1_1") (pintype "bidirectional"))
      (node (ref "R65") (pin "1") (pinfunction "1_1") (pintype "bidirectional"))
      (node (ref "R70") (pin "1") (pinfunction "1_1") (pintype "bidirectional"))
      (node (ref "R79") (pin "1") (pinfunction "1_1") (pintype "bidirectional"))
      (node (ref "R84") (pin "1") (pinfunction "1_1") (pintype "bidirectional"))
      (node (ref "R9") (pin "1") (pinfunction "1_1") (pintype "bidirectional"))
      (node (ref "R93") (pin "1") (pinfunction "1_1") (pintype "bidirectional"))
      (node (ref "R98") (pin "1") (pinfunction "1_1") (pintype "bidirectional"))
      (node (ref "TP11") (pin "1") (pinfunction "P$1_1") (pintype "bidirectional"))
      (node (ref "TP17") (pin "1") (pinfunction "P$1_1") (pintype "bidirectional"))
      (node (ref "TP2") (pin "1") (pinfunction "P$1_1") (pintype "bidirectional"))
      (node (ref "TP23") (pin "1") (pinfunction "P$1_1") (pintype "bidirectional"))
      (node (ref "TP29") (pin "1") (pinfunction "P$1_1") (pintype "bidirectional"))
      (node (ref "TP35") (pin "1") (pinfunction "P$1_1") (pintype "bidirectional"))
      (node (ref "TP41") (pin "1") (pinfunction "P$1_1") (pintype "bidirectional"))
      (node (ref "TP47") (pin "1") (pinfunction "P$1_1") (pintype "bidirectional"))
      (node (ref "TP5") (pin "1") (pinfunction "P$1_1") (pintype "bidirectional"))
      (node (ref "U2") (pin "1") (pinfunction "VIN-_1") (pintype "bidirectional"))
      (node (ref "U2") (pin "4") (pinfunction "COM_4") (pintype "bidirectional"))
    )
    (net (code "2") (name "Net-(C3-Pad2)") (class "Default")
      (node (ref "C3") (pin "2") (pinfunction "2_2") (pintype "bidirectional"))
      (node (ref "C7") (pin "2") (pinfunction "2_2") (pintype "bidirectional"))
      (node (ref "R8") (pin "1") (pinfunction "1_1") (pintype "bidirectional"))
    )
    (net (code "3") (name "Net-(C4-Pad2)") (class "Default")
      (node (ref "C4") (pin "2") (pinfunction "2_2") (pintype "bidirectional"))
      (node (ref "C8") (pin "2") (pinfunction "2_2") (pintype "bidirectional"))
      (node (ref "R10") (pin "1") (pinfunction "1_1") (pintype "bidirectional"))
    )
    (net (code "4") (name "Net-(C7-Pad1)") (class "Default")
      (node (ref "C7") (pin "1") (pinfunction "1_1") (pintype "bidirectional"))
      (node (ref "CN2") (pin "2") (pinfunction "2_2") (pintype "bidirectional"))
    )
    (net (code "5") (name "Net-(C8-Pad1)") (class "Default")
      (node (ref "C8") (pin "1") (pinfunction "1_1") (pintype "bidirectional"))
      (node (ref "CN2") (pin "3") (pinfunction "3_3") (pintype "bidirectional"))
    )
    (net (code "6") (name "Net-(C19-Pad2)") (class "Default")
      (node (ref "C19") (pin "2") (pinfunction "2_2") (pintype "bidirectional"))
      (node (ref "C23") (pin "2") (pinfunction "2_2") (pintype "bidirectional"))
      (node (ref "R22") (pin "1") (pinfunction "1_1") (pintype "bidirectional"))
    )
    (net (code "7") (name "Net-(C20-Pad2)") (class "Default")
      (node (ref "C20") (pin "2") (pinfunction "2_2") (pintype "bidirectional"))
      (node (ref "C24") (pin "2") (pinfunction "2_2") (pintype "bidirectional"))
      (node (ref "R24") (pin "1") (pinfunction "1_1") (pintype "bidirectional"))
    )
    (net (code "8") (name "Net-(C23-Pad1)") (class "Default")
      (node (ref "C23") (pin "1") (pinfunction "1_1") (pintype "bidirectional"))
      (node (ref "CN4") (pin "2") (pinfunction "2_2") (pintype "bidirectional"))
    )
    (net (code "9") (name "Net-(C24-Pad1)") (class "Default")
      (node (ref "C24") (pin "1") (pinfunction "1_1") (pintype "bidirectional"))
      (node (ref "CN4") (pin "3") (pinfunction "3_3") (pintype "bidirectional"))
    )
    (net (code "10") (name "Net-(C31-Pad2)") (class "Default")
      (node (ref "C31") (pin "2") (pinfunction "2_2") (pintype "bidirectional"))
      (node (ref "C35") (pin "2") (pinfunction "2_2") (pintype "bidirectional"))
      (node (ref "R36") (pin "1") (pinfunction "1_1") (pintype "bidirectional"))
    )
    (net (code "11") (name "Net-(C32-Pad2)") (class "Default")
      (node (ref "C32") (pin "2") (pinfunction "2_2") (pintype "bidirectional"))
      (node (ref "C36") (pin "2") (pinfunction "2_2") (pintype "bidirectional"))
      (node (ref "R38") (pin "1") (pinfunction "1_1") (pintype "bidirectional"))
    )
    (net (code "12") (name "Net-(C35-Pad1)") (class "Default")
      (node (ref "C35") (pin "1") (pinfunction "1_1") (pintype "bidirectional"))
      (node (ref "CN6") (pin "2") (pinfunction "2_2") (pintype "bidirectional"))
    )
    (net (code "13") (name "Net-(C36-Pad1)") (class "Default")
      (node (ref "C36") (pin "1") (pinfunction "1_1") (pintype "bidirectional"))
      (node (ref "CN6") (pin "3") (pinfunction "3_3") (pintype "bidirectional"))
    )
    (net (code "14") (name "Net-(C43-Pad2)") (class "Default")
      (node (ref "C43") (pin "2") (pinfunction "2_2") (pintype "bidirectional"))
      (node (ref "C47") (pin "2") (pinfunction "2_2") (pintype "bidirectional"))
      (node (ref "R50") (pin "1") (pinfunction "1_1") (pintype "bidirectional"))
    )
    (net (code "15") (name "Net-(C44-Pad2)") (class "Default")
      (node (ref "C44") (pin "2") (pinfunction "2_2") (pintype "bidirectional"))
      (node (ref "C48") (pin "2") (pinfunction "2_2") (pintype "bidirectional"))
      (node (ref "R52") (pin "1") (pinfunction "1_1") (pintype "bidirectional"))
    )
    (net (code "16") (name "Net-(C47-Pad1)") (class "Default")
      (node (ref "C47") (pin "1") (pinfunction "1_1") (pintype "bidirectional"))
      (node (ref "CN8") (pin "2") (pinfunction "2_2") (pintype "bidirectional"))
    )
    (net (code "17") (name "Net-(C48-Pad1)") (class "Default")
      (node (ref "C48") (pin "1") (pinfunction "1_1") (pintype "bidirectional"))
      (node (ref "CN8") (pin "3") (pinfunction "3_3") (pintype "bidirectional"))
    )
    (net (code "18") (name "Net-(C55-Pad2)") (class "Default")
      (node (ref "C55") (pin "2") (pinfunction "2_2") (pintype "bidirectional"))
      (node (ref "C59") (pin "2") (pinfunction "2_2") (pintype "bidirectional"))
      (node (ref "R64") (pin "1") (pinfunction "1_1") (pintype "bidirectional"))
    )
    (net (code "19") (name "Net-(C56-Pad2)") (class "Default")
      (node (ref "C56") (pin "2") (pinfunction "2_2") (pintype "bidirectional"))
      (node (ref "C60") (pin "2") (pinfunction "2_2") (pintype "bidirectional"))
      (node (ref "R66") (pin "1") (pinfunction "1_1") (pintype "bidirectional"))
    )
    (net (code "20") (name "Net-(C59-Pad1)") (class "Default")
      (node (ref "C59") (pin "1") (pinfunction "1_1") (pintype "bidirectional"))
      (node (ref "CN10") (pin "2") (pinfunction "2_2") (pintype "bidirectional"))
    )
    (net (code "21") (name "Net-(C60-Pad1)") (class "Default")
      (node (ref "C60") (pin "1") (pinfunction "1_1") (pintype "bidirectional"))
      (node (ref "CN10") (pin "3") (pinfunction "3_3") (pintype "bidirectional"))
    )
    (net (code "22") (name "Net-(C67-Pad2)") (class "Default")
      (node (ref "C67") (pin "2") (pinfunction "2_2") (pintype "bidirectional"))
      (node (ref "C71") (pin "2") (pinfunction "2_2") (pintype "bidirectional"))
      (node (ref "R78") (pin "1") (pinfunction "1_1") (pintype "bidirectional"))
    )
    (net (code "23") (name "Net-(C68-Pad2)") (class "Default")
      (node (ref "C68") (pin "2") (pinfunction "2_2") (pintype "bidirectional"))
      (node (ref "C72") (pin "2") (pinfunction "2_2") (pintype "bidirectional"))
      (node (ref "R80") (pin "1") (pinfunction "1_1") (pintype "bidirectional"))
    )
    (net (code "24") (name "Net-(C71-Pad1)") (class "Default")
      (node (ref "C71") (pin "1") (pinfunction "1_1") (pintype "bidirectional"))
      (node (ref "CN12") (pin "2") (pinfunction "2_2") (pintype "bidirectional"))
    )
    (net (code "25") (name "Net-(C72-Pad1)") (class "Default")
      (node (ref "C72") (pin "1") (pinfunction "1_1") (pintype "bidirectional"))
      (node (ref "CN12") (pin "3") (pinfunction "3_3") (pintype "bidirectional"))
    )
    (net (code "26") (name "Net-(C79-Pad2)") (class "Default")
      (node (ref "C79") (pin "2") (pinfunction "2_2") (pintype "bidirectional"))
      (node (ref "C83") (pin "2") (pinfunction "2_2") (pintype "bidirectional"))
      (node (ref "R92") (pin "1") (pinfunction "1_1") (pintype "bidirectional"))
    )
    (net (code "27") (name "Net-(C80-Pad2)") (class "Default")
      (node (ref "C80") (pin "2") (pinfunction "2_2") (pintype "bidirectional"))
      (node (ref "C84") (pin "2") (pinfunction "2_2") (pintype "bidirectional"))
      (node (ref "R94") (pin "1") (pinfunction "1_1") (pintype "bidirectional"))
    )
    (net (code "28") (name "Net-(C83-Pad1)") (class "Default")
      (node (ref "C83") (pin "1") (pinfunction "1_1") (pintype "bidirectional"))
      (node (ref "CN14") (pin "2") (pinfunction "2_2") (pintype "bidirectional"))
    )
    (net (code "29") (name "Net-(C84-Pad1)") (class "Default")
      (node (ref "C84") (pin "1") (pinfunction "1_1") (pintype "bidirectional"))
      (node (ref "CN14") (pin "3") (pinfunction "3_3") (pintype "bidirectional"))
    )
    (net (code "30") (name "Net-(C91-Pad2)") (class "Default")
      (node (ref "C91") (pin "2") (pinfunction "2_2") (pintype "bidirectional"))
      (node (ref "C95") (pin "2") (pinfunction "2_2") (pintype "bidirectional"))
      (node (ref "R106") (pin "1") (pinfunction "1_1") (pintype "bidirectional"))
    )
    (net (code "31") (name "Net-(C92-Pad2)") (class "Default")
      (node (ref "C92") (pin "2") (pinfunction "2_2") (pintype "bidirectional"))
      (node (ref "C96") (pin "2") (pinfunction "2_2") (pintype "bidirectional"))
      (node (ref "R108") (pin "1") (pinfunction "1_1") (pintype "bidirectional"))
    )
    (net (code "32") (name "Net-(C95-Pad1)") (class "Default")
      (node (ref "C95") (pin "1") (pinfunction "1_1") (pintype "bidirectional"))
      (node (ref "CN16") (pin "2") (pinfunction "2_2") (pintype "bidirectional"))
    )
    (net (code "33") (name "Net-(C96-Pad1)") (class "Default")
      (node (ref "C96") (pin "1") (pinfunction "1_1") (pintype "bidirectional"))
      (node (ref "CN16") (pin "3") (pinfunction "3_3") (pintype "bidirectional"))
    )
    (net (code "34") (name "Net-(TP1-P$1)") (class "Default")
      (node (ref "TP1") (pin "1") (pinfunction "P$1_1") (pintype "bidirectional"))
      (node (ref "U2") (pin "2") (pinfunction "VIN+_2") (pintype "bidirectional"))
    )
    (net (code "35") (name "Net-(TP4-P$1)") (class "Default")
      (node (ref "R11") (pin "1") (pinfunction "1_1") (pintype "bidirectional"))
      (node (ref "R12") (pin "2") (pinfunction "2_2") (pintype "bidirectional"))
      (node (ref "TP4") (pin "1") (pinfunction "P$1_1") (pintype "bidirectional"))
      (node (ref "U1") (pin "1") (pinfunction "OUT_1") (pintype "bidirectional"))
    )
    (net (code "36") (name "Net-(TP6-P$1)") (class "Default")
      (node (ref "R13") (pin "1") (pinfunction "1_1") (pintype "bidirectional"))
      (node (ref "TP6") (pin "1") (pinfunction "P$1_1") (pintype "bidirectional"))
      (node (ref "U1") (pin "7") (pinfunction "OUT_7") (pintype "bidirectional"))
    )
    (net (code "37") (name "Net-(TP10-P$1)") (class "Default")
      (node (ref "R25") (pin "1") (pinfunction "1_1") (pintype "bidirectional"))
      (node (ref "R26") (pin "2") (pinfunction "2_2") (pintype "bidirectional"))
      (node (ref "TP10") (pin "1") (pinfunction "P$1_1") (pintype "bidirectional"))
      (node (ref "U4") (pin "1") (pinfunction "OUT_1") (pintype "bidirectional"))
    )
    (net (code "38") (name "Net-(TP12-P$1)") (class "Default")
      (node (ref "R27") (pin "1") (pinfunction "1_1") (pintype "bidirectional"))
      (node (ref "TP12") (pin "1") (pinfunction "P$1_1") (pintype "bidirectional"))
      (node (ref "U4") (pin "7") (pinfunction "OUT_7") (pintype "bidirectional"))
    )
    (net (code "39") (name "Net-(TP16-P$1)") (class "Default")
      (node (ref "R39") (pin "1") (pinfunction "1_1") (pintype "bidirectional"))
      (node (ref "R40") (pin "2") (pinfunction "2_2") (pintype "bidirectional"))
      (node (ref "TP16") (pin "1") (pinfunction "P$1_1") (pintype "bidirectional"))
      (node (ref "U6") (pin "1") (pinfunction "OUT_1") (pintype "bidirectional"))
    )
    (net (code "40") (name "Net-(TP18-P$1)") (class "Default")
      (node (ref "R41") (pin "1") (pinfunction "1_1") (pintype "bidirectional"))
      (node (ref "TP18") (pin "1") (pinfunction "P$1_1") (pintype "bidirectional"))
      (node (ref "U6") (pin "7") (pinfunction "OUT_7") (pintype "bidirectional"))
    )
    (net (code "41") (name "Net-(TP22-P$1)") (class "Default")
      (node (ref "R53") (pin "1") (pinfunction "1_1") (pintype "bidirectional"))
      (node (ref "R54") (pin "2") (pinfunction "2_2") (pintype "bidirectional"))
      (node (ref "TP22") (pin "1") (pinfunction "P$1_1") (pintype "bidirectional"))
      (node (ref "U8") (pin "1") (pinfunction "OUT_1") (pintype "bidirectional"))
    )
    (net (code "42") (name "Net-(TP24-P$1)") (class "Default")
      (node (ref "R55") (pin "1") (pinfunction "1_1") (pintype "bidirectional"))
      (node (ref "TP24") (pin "1") (pinfunction "P$1_1") (pintype "bidirectional"))
      (node (ref "U8") (pin "7") (pinfunction "OUT_7") (pintype "bidirectional"))
    )
    (net (code "43") (name "Net-(TP28-P$1)") (class "Default")
      (node (ref "R67") (pin "1") (pinfunction "1_1") (pintype "bidirectional"))
      (node (ref "R68") (pin "2") (pinfunction "2_2") (pintype "bidirectional"))
      (node (ref "TP28") (pin "1") (pinfunction "P$1_1") (pintype "bidirectional"))
      (node (ref "U10") (pin "1") (pinfunction "OUT_1") (pintype "bidirectional"))
    )
    (net (code "44") (name "Net-(TP30-P$1)") (class "Default")
      (node (ref "R69") (pin "1") (pinfunction "1_1") (pintype "bidirectional"))
      (node (ref "TP30") (pin "1") (pinfunction "P$1_1") (pintype "bidirectional"))
      (node (ref "U10") (pin "7") (pinfunction "OUT_7") (pintype "bidirectional"))
    )
    (net (code "45") (name "Net-(TP34-P$1)") (class "Default")
      (node (ref "R81") (pin "1") (pinfunction "1_1") (pintype "bidirectional"))
      (node (ref "R82") (pin "2") (pinfunction "2_2") (pintype "bidirectional"))
      (node (ref "TP34") (pin "1") (pinfunction "P$1_1") (pintype "bidirectional"))
      (node (ref "U12") (pin "1") (pinfunction "OUT_1") (pintype "bidirectional"))
    )
    (net (code "46") (name "Net-(TP36-P$1)") (class "Default")
      (node (ref "R83") (pin "1") (pinfunction "1_1") (pintype "bidirectional"))
      (node (ref "TP36") (pin "1") (pinfunction "P$1_1") (pintype "bidirectional"))
      (node (ref "U12") (pin "7") (pinfunction "OUT_7") (pintype "bidirectional"))
    )
    (net (code "47") (name "Net-(TP40-P$1)") (class "Default")
      (node (ref "R95") (pin "1") (pinfunction "1_1") (pintype "bidirectional"))
      (node (ref "R96") (pin "2") (pinfunction "2_2") (pintype "bidirectional"))
      (node (ref "TP40") (pin "1") (pinfunction "P$1_1") (pintype "bidirectional"))
      (node (ref "U14") (pin "1") (pinfunction "OUT_1") (pintype "bidirectional"))
    )
    (net (code "48") (name "Net-(TP42-P$1)") (class "Default")
      (node (ref "R97") (pin "1") (pinfunction "1_1") (pintype "bidirectional"))
      (node (ref "TP42") (pin "1") (pinfunction "P$1_1") (pintype "bidirectional"))
      (node (ref "U14") (pin "7") (pinfunction "OUT_7") (pintype "bidirectional"))
    )
    (net (code "49") (name "Net-(TP46-P$1)") (class "Default")
      (node (ref "R109") (pin "1") (pinfunction "1_1") (pintype "bidirectional"))
      (node (ref "R110") (pin "2") (pinfunction "2_2") (pintype "bidirectional"))
      (node (ref "TP46") (pin "1") (pinfunction "P$1_1") (pintype "bidirectional"))
      (node (ref "U16") (pin "1") (pinfunction "OUT_1") (pintype "bidirectional"))
    )
    (net (code "50") (name "Net-(TP48-P$1)") (class "Default")
      (node (ref "R111") (pin "1") (pinfunction "1_1") (pintype "bidirectional"))
      (node (ref "TP48") (pin "1") (pinfunction "P$1_1") (pintype "bidirectional"))
      (node (ref "U16") (pin "7") (pinfunction "OUT_7") (pintype "bidirectional"))
    )
    (net (code "51") (name "Net-(U1A-+)") (class "Default")
      (node (ref "R8") (pin "2") (pinfunction "2_2") (pintype "bidirectional"))
      (node (ref "R9") (pin "2") (pinfunction "2_2") (pintype "bidirectional"))
      (node (ref "U1") (pin "3") (pinfunction "+_3") (pintype "bidirectional"))
    )
    (net (code "52") (name "Net-(U1A--)") (class "Default")
      (node (ref "R10") (pin "2") (pinfunction "2_2") (pintype "bidirectional"))
      (node (ref "R11") (pin "2") (pinfunction "2_2") (pintype "bidirectional"))
      (node (ref "U1") (pin "2") (pinfunction "-_2") (pintype "bidirectional"))
    )
    (net (code "53") (name "Net-(U1B-+)") (class "Default")
      (node (ref "R14") (pin "2") (pinfunction "2_2") (pintype "bidirectional"))
      (node (ref "U1") (pin "5") (pinfunction "+_5") (pintype "bidirectional"))
    )
    (net (code "54") (name "Net-(U1B--)") (class "Default")
      (node (ref "R12") (pin "1") (pinfunction "1_1") (pintype "bidirectional"))
      (node (ref "R13") (pin "2") (pinfunction "2_2") (pintype "bidirectional"))
      (node (ref "U1") (pin "6") (pinfunction "-_6") (pintype "bidirectional"))
    )
    (net (code "55") (name "Net-(U4A-+)") (class "Default")
      (node (ref "R22") (pin "2") (pinfunction "2_2") (pintype "bidirectional"))
      (node (ref "R23") (pin "2") (pinfunction "2_2") (pintype "bidirectional"))
      (node (ref "U4") (pin "3") (pinfunction "+_3") (pintype "bidirectional"))
    )
    (net (code "56") (name "Net-(U4A--)") (class "Default")
      (node (ref "R24") (pin "2") (pinfunction "2_2") (pintype "bidirectional"))
      (node (ref "R25") (pin "2") (pinfunction "2_2") (pintype "bidirectional"))
      (node (ref "U4") (pin "2") (pinfunction "-_2") (pintype "bidirectional"))
    )
    (net (code "57") (name "Net-(U4B-+)") (class "Default")
      (node (ref "R28") (pin "2") (pinfunction "2_2") (pintype "bidirectional"))
      (node (ref "U4") (pin "5") (pinfunction "+_5") (pintype "bidirectional"))
    )
    (net (code "58") (name "Net-(U4B--)") (class "Default")
      (node (ref "R26") (pin "1") (pinfunction "1_1") (pintype "bidirectional"))
      (node (ref "R27") (pin "2") (pinfunction "2_2") (pintype "bidirectional"))
      (node (ref "U4") (pin "6") (pinfunction "-_6") (pintype "bidirectional"))
    )
    (net (code "59") (name "Net-(U6A-+)") (class "Default")
      (node (ref "R36") (pin "2") (pinfunction "2_2") (pintype "bidirectional"))
      (node (ref "R37") (pin "2") (pinfunction "2_2") (pintype "bidirectional"))
      (node (ref "U6") (pin "3") (pinfunction "+_3") (pintype "bidirectional"))
    )
    (net (code "60") (name "Net-(U6A--)") (class "Default")
      (node (ref "R38") (pin "2") (pinfunction "2_2") (pintype "bidirectional"))
      (node (ref "R39") (pin "2") (pinfunction "2_2") (pintype "bidirectional"))
      (node (ref "U6") (pin "2") (pinfunction "-_2") (pintype "bidirectional"))
    )
    (net (code "61") (name "Net-(U6B-+)") (class "Default")
      (node (ref "R42") (pin "2") (pinfunction "2_2") (pintype "bidirectional"))
      (node (ref "U6") (pin "5") (pinfunction "+_5") (pintype "bidirectional"))
    )
    (net (code "62") (name "Net-(U6B--)") (class "Default")
      (node (ref "R40") (pin "1") (pinfunction "1_1") (pintype "bidirectional"))
      (node (ref "R41") (pin "2") (pinfunction "2_2") (pintype "bidirectional"))
      (node (ref "U6") (pin "6") (pinfunction "-_6") (pintype "bidirectional"))
    )
    (net (code "63") (name "Net-(U8A-+)") (class "Default")
      (node (ref "R50") (pin "2") (pinfunction "2_2") (pintype "bidirectional"))
      (node (ref "R51") (pin "2") (pinfunction "2_2") (pintype "bidirectional"))
      (node (ref "U8") (pin "3") (pinfunction "+_3") (pintype "bidirectional"))
    )
    (net (code "64") (name "Net-(U8A--)") (class "Default")
      (node (ref "R52") (pin "2") (pinfunction "2_2") (pintype "bidirectional"))
      (node (ref "R53") (pin "2") (pinfunction "2_2") (pintype "bidirectional"))
      (node (ref "U8") (pin "2") (pinfunction "-_2") (pintype "bidirectional"))
    )
    (net (code "65") (name "Net-(U8B-+)") (class "Default")
      (node (ref "R56") (pin "2") (pinfunction "2_2") (pintype "bidirectional"))
      (node (ref "U8") (pin "5") (pinfunction "+_5") (pintype "bidirectional"))
    )
    (net (code "66") (name "Net-(U8B--)") (class "Default")
      (node (ref "R54") (pin "1") (pinfunction "1_1") (pintype "bidirectional"))
      (node (ref "R55") (pin "2") (pinfunction "2_2") (pintype "bidirectional"))
      (node (ref "U8") (pin "6") (pinfunction "-_6") (pintype "bidirectional"))
    )
    (net (code "67") (name "Net-(U10A-+)") (class "Default")
      (node (ref "R64") (pin "2") (pinfunction "2_2") (pintype "bidirectional"))
      (node (ref "R65") (pin "2") (pinfunction "2_2") (pintype "bidirectional"))
      (node (ref "U10") (pin "3") (pinfunction "+_3") (pintype "bidirectional"))
    )
    (net (code "68") (name "Net-(U10A--)") (class "Default")
      (node (ref "R66") (pin "2") (pinfunction "2_2") (pintype "bidirectional"))
      (node (ref "R67") (pin "2") (pinfunction "2_2") (pintype "bidirectional"))
      (node (ref "U10") (pin "2") (pinfunction "-_2") (pintype "bidirectional"))
    )
    (net (code "69") (name "Net-(U10B-+)") (class "Default")
      (node (ref "R70") (pin "2") (pinfunction "2_2") (pintype "bidirectional"))
      (node (ref "U10") (pin "5") (pinfunction "+_5") (pintype "bidirectional"))
    )
    (net (code "70") (name "Net-(U10B--)") (class "Default")
      (node (ref "R68") (pin "1") (pinfunction "1_1") (pintype "bidirectional"))
      (node (ref "R69") (pin "2") (pinfunction "2_2") (pintype "bidirectional"))
      (node (ref "U10") (pin "6") (pinfunction "-_6") (pintype "bidirectional"))
    )
    (net (code "71") (name "Net-(U12A-+)") (class "Default")
      (node (ref "R78") (pin "2") (pinfunction "2_2") (pintype "bidirectional"))
      (node (ref "R79") (pin "2") (pinfunction "2_2") (pintype "bidirectional"))
      (node (ref "U12") (pin "3") (pinfunction "+_3") (pintype "bidirectional"))
    )
    (net (code "72") (name "Net-(U12A--)") (class "Default")
      (node (ref "R80") (pin "2") (pinfunction "2_2") (pintype "bidirectional"))
      (node (ref "R81") (pin "2") (pinfunction "2_2") (pintype "bidirectional"))
      (node (ref "U12") (pin "2") (pinfunction "-_2") (pintype "bidirectional"))
    )
    (net (code "73") (name "Net-(U12B-+)") (class "Default")
      (node (ref "R84") (pin "2") (pinfunction "2_2") (pintype "bidirectional"))
      (node (ref "U12") (pin "5") (pinfunction "+_5") (pintype "bidirectional"))
    )
    (net (code "74") (name "Net-(U12B--)") (class "Default")
      (node (ref "R82") (pin "1") (pinfunction "1_1") (pintype "bidirectional"))
      (node (ref "R83") (pin "2") (pinfunction "2_2") (pintype "bidirectional"))
      (node (ref "U12") (pin "6") (pinfunction "-_6") (pintype "bidirectional"))
    )
    (net (code "75") (name "Net-(U14A-+)") (class "Default")
      (node (ref "R92") (pin "2") (pinfunction "2_2") (pintype "bidirectional"))
      (node (ref "R93") (pin "2") (pinfunction "2_2") (pintype "bidirectional"))
      (node (ref "U14") (pin "3") (pinfunction "+_3") (pintype "bidirectional"))
    )
    (net (code "76") (name "Net-(U14A--)") (class "Default")
      (node (ref "R94") (pin "2") (pinfunction "2_2") (pintype "bidirectional"))
      (node (ref "R95") (pin "2") (pinfunction "2_2") (pintype "bidirectional"))
      (node (ref "U14") (pin "2") (pinfunction "-_2") (pintype "bidirectional"))
    )
    (net (code "77") (name "Net-(U14B-+)") (class "Default")
      (node (ref "R98") (pin "2") (pinfunction "2_2") (pintype "bidirectional"))
      (node (ref "U14") (pin "5") (pinfunction "+_5") (pintype "bidirectional"))
    )
    (net (code "78") (name "Net-(U14B--)") (class "Default")
      (node (ref "R96") (pin "1") (pinfunction "1_1") (pintype "bidirectional"))
      (node (ref "R97") (pin "2") (pinfunction "2_2") (pintype "bidirectional"))
      (node (ref "U14") (pin "6") (pinfunction "-_6") (pintype "bidirectional"))
    )
    (net (code "79") (name "Net-(U16A-+)") (class "Default")
      (node (ref "R106") (pin "2") (pinfunction "2_2") (pintype "bidirectional"))
      (node (ref "R107") (pin "2") (pinfunction "2_2") (pintype "bidirectional"))
      (node (ref "U16") (pin "3") (pinfunction "+_3") (pintype "bidirectional"))
    )
    (net (code "80") (name "Net-(U16A--)") (class "Default")
      (node (ref "R108") (pin "2") (pinfunction "2_2") (pintype "bidirectional"))
      (node (ref "R109") (pin "2") (pinfunction "2_2") (pintype "bidirectional"))
      (node (ref "U16") (pin "2") (pinfunction "-_2") (pintype "bidirectional"))
    )
    (net (code "81") (name "Net-(U16B-+)") (class "Default")
      (node (ref "R112") (pin "2") (pinfunction "2_2") (pintype "bidirectional"))
      (node (ref "U16") (pin "5") (pinfunction "+_5") (pintype "bidirectional"))
    )
    (net (code "82") (name "Net-(U16B--)") (class "Default")
      (node (ref "R110") (pin "1") (pinfunction "1_1") (pintype "bidirectional"))
      (node (ref "R111") (pin "2") (pinfunction "2_2") (pintype "bidirectional"))
      (node (ref "U16") (pin "6") (pinfunction "-_6") (pintype "bidirectional"))
    )
    (net (code "83") (name "V+") (class "Default")
      (node (ref "C21") (pin "2") (pinfunction "2_2") (pintype "bidirectional"))
      (node (ref "C33") (pin "2") (pinfunction "2_2") (pintype "bidirectional"))
      (node (ref "C45") (pin "2") (pinfunction "2_2") (pintype "bidirectional"))
      (node (ref "C5") (pin "2") (pinfunction "2_2") (pintype "bidirectional"))
      (node (ref "C57") (pin "2") (pinfunction "2_2") (pintype "bidirectional"))
      (node (ref "C69") (pin "2") (pinfunction "2_2") (pintype "bidirectional"))
      (node (ref "C81") (pin "2") (pinfunction "2_2") (pintype "bidirectional"))
      (node (ref "C93") (pin "2") (pinfunction "2_2") (pintype "bidirectional"))
      (node (ref "U1") (pin "8") (pinfunction "V+_8") (pintype "bidirectional"))
      (node (ref "U10") (pin "8") (pinfunction "V+_8") (pintype "bidirectional"))
      (node (ref "U12") (pin "8") (pinfunction "V+_8") (pintype "bidirectional"))
      (node (ref "U14") (pin "8") (pinfunction "V+_8") (pintype "bidirectional"))
      (node (ref "U16") (pin "8") (pinfunction "V+_8") (pintype "bidirectional"))
      (node (ref "U2") (pin "3") (pinfunction "VO+_3") (pintype "bidirectional"))
      (node (ref "U4") (pin "8") (pinfunction "V+_8") (pintype "bidirectional"))
      (node (ref "U6") (pin "8") (pinfunction "V+_8") (pintype "bidirectional"))
      (node (ref "U8") (pin "8") (pinfunction "V+_8") (pintype "bidirectional"))
    )
    (net (code "84") (name "V-") (class "Default")
      (node (ref "C22") (pin "2") (pinfunction "2_2") (pintype "bidirectional"))
      (node (ref "C34") (pin "2") (pinfunction "2_2") (pintype "bidirectional"))
      (node (ref "C46") (pin "2") (pinfunction "2_2") (pintype "bidirectional"))
      (node (ref "C58") (pin "2") (pinfunction "2_2") (pintype "bidirectional"))
      (node (ref "C6") (pin "2") (pinfunction "2_2") (pintype "bidirectional"))
      (node (ref "C70") (pin "2") (pinfunction "2_2") (pintype "bidirectional"))
      (node (ref "C82") (pin "2") (pinfunction "2_2") (pintype "bidirectional"))
      (node (ref "C94") (pin "2") (pinfunction "2_2") (pintype "bidirectional"))
      (node (ref "U1") (pin "4") (pinfunction "V-_4") (pintype "bidirectional"))
      (node (ref "U10") (pin "4") (pinfunction "V-_4") (pintype "bidirectional"))
      (node (ref "U12") (pin "4") (pinfunction "V-_4") (pintype "bidirectional"))
      (node (ref "U14") (pin "4") (pinfunction "V-_4") (pintype "bidirectional"))
      (node (ref "U16") (pin "4") (pinfunction "V-_4") (pintype "bidirectional"))
      (node (ref "U2") (pin "5") (pinfunction "VO-_5") (pintype "bidirectional"))
      (node (ref "U4") (pin "4") (pinfunction "V-_4") (pintype "bidirectional"))
      (node (ref "U6") (pin "4") (pinfunction "V-_4") (pintype "bidirectional"))
      (node (ref "U8") (pin "4") (pinfunction "V-_4") (pintype "bidirectional"))
    )
  )
)
